# MCU.net
KiCad netlist of a schematic drawn in Altium Designer
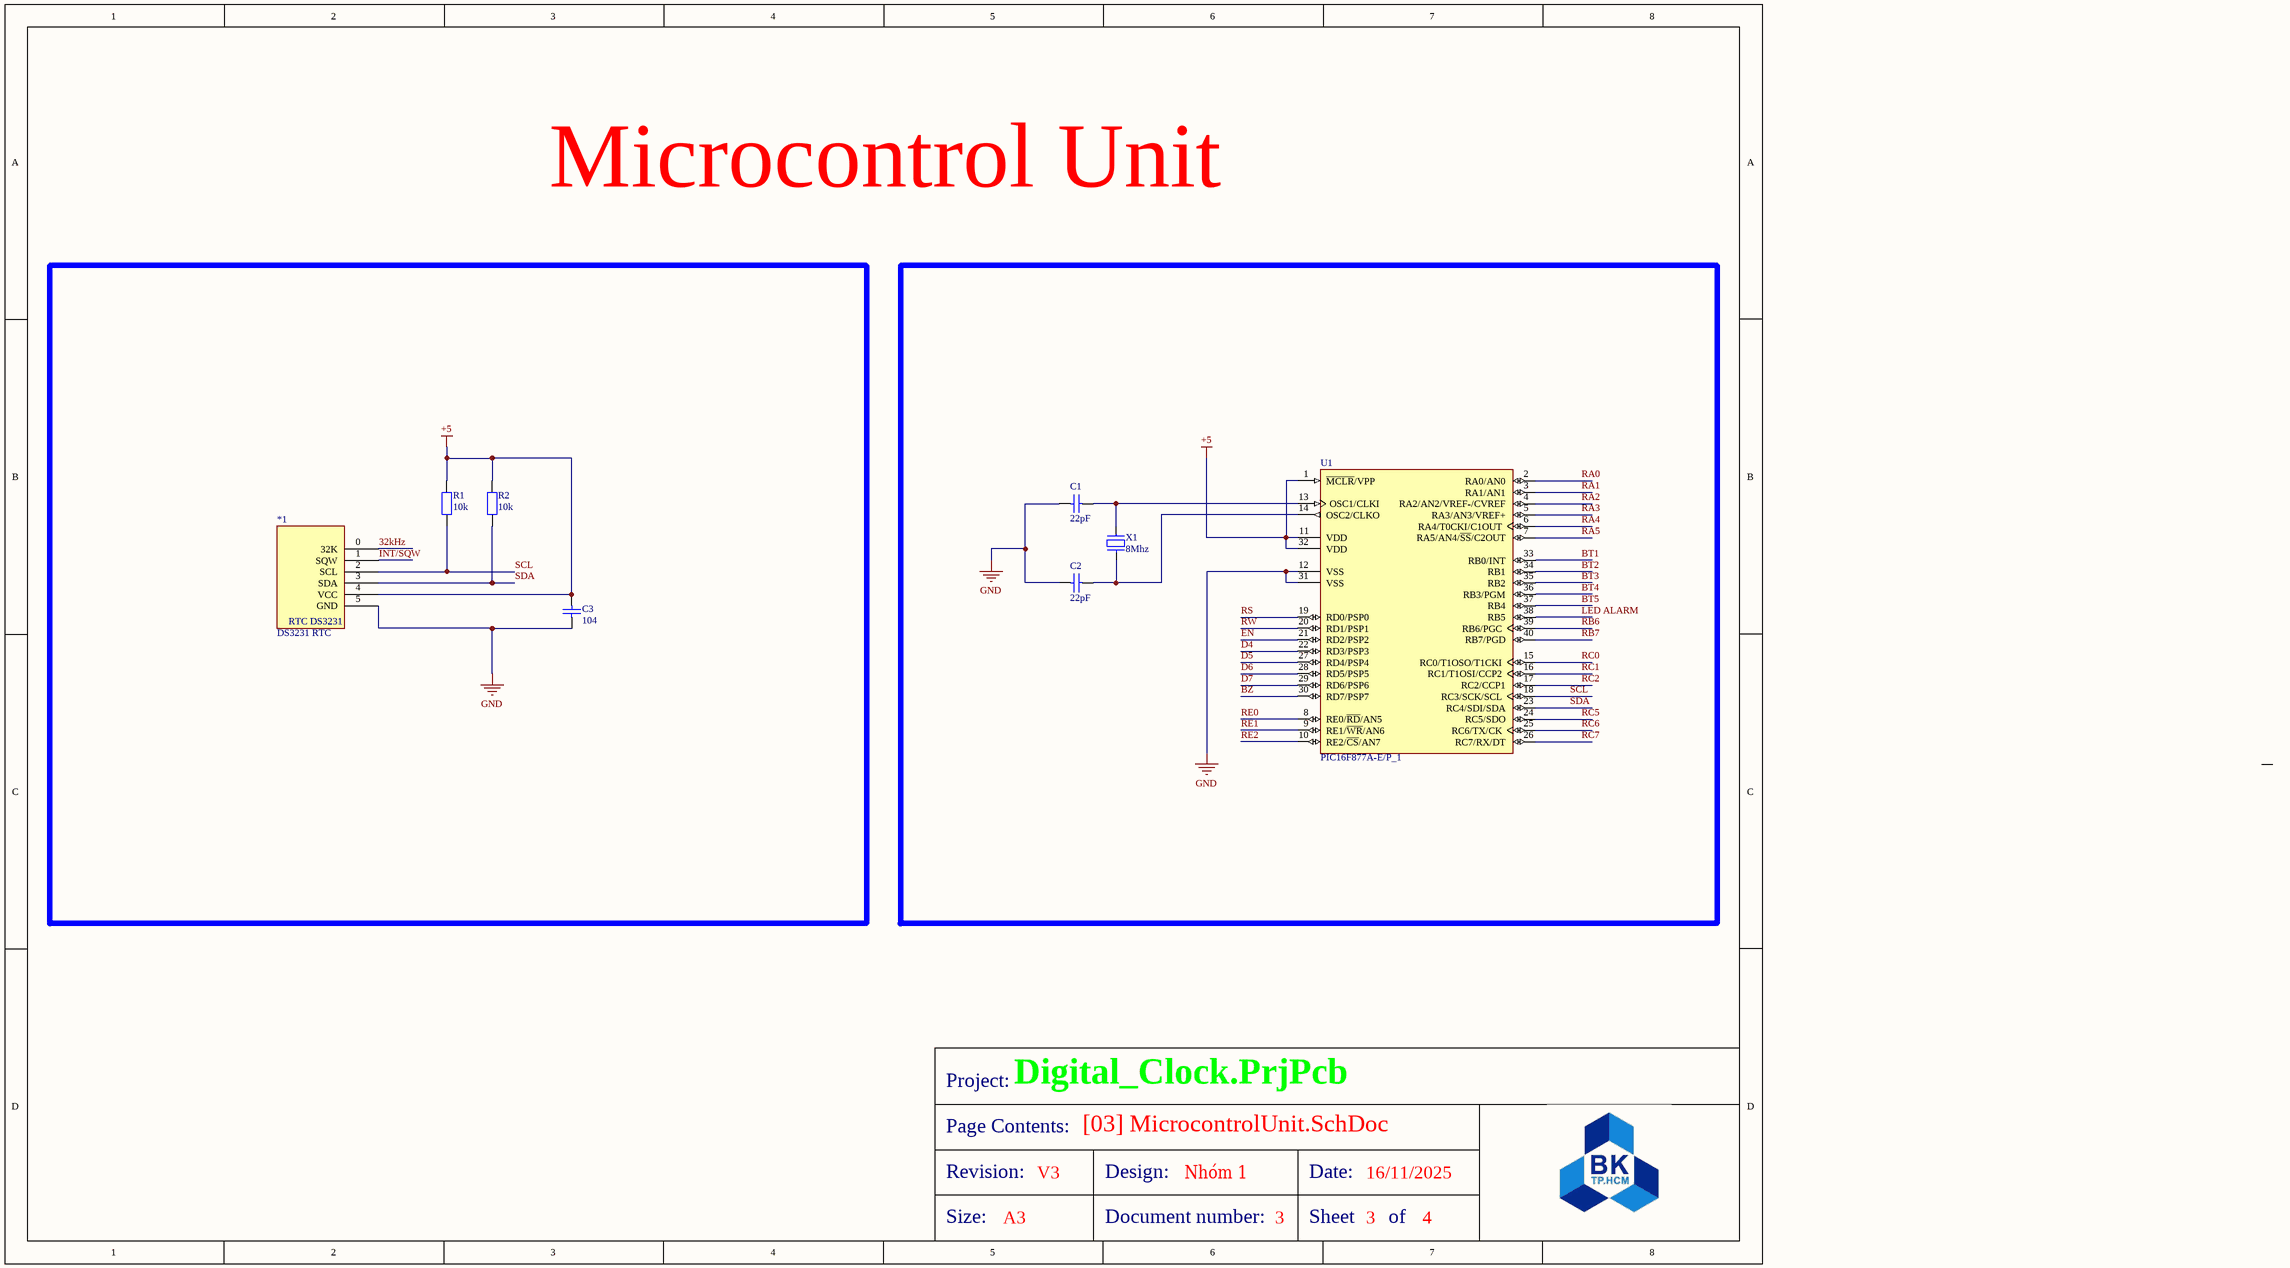
[diagram p0: MCU.SchDoc]

(export (version "E")
  (design (tool "Eeschema 10.0.6"))
  (components
    (comp (ref "*1")
      (value "DS3231 RTC")
      (footprint "2RTC-DS3231-MODULE")
      (libsource (lib "lk") (part "DS3231 RTC"))
    )
    (comp (ref "C1")
      (value "22pF")
      (footprint "tu gom")
      (description "Cắm")
      (libsource (lib "Capacitor") (part "Tu gom 22pF 50V"))
    )
    (comp (ref "C2")
      (value "22pF")
      (footprint "tu gom")
      (description "Cắm")
      (libsource (lib "Capacitor") (part "Tu gom 22pF 50V"))
    )
    (comp (ref "C3")
      (value "104")
      (footprint "tu gom")
      (description "Cắm")
      (libsource (lib "Capacitor") (part "Tu gom 104 50V"))
    )
    (comp (ref "R1")
      (value "10k")
      (footprint "R1/4W")
      (description "Resistor 1/4W")
      (libsource (lib "My Library") (part "R1/4W"))
    )
    (comp (ref "R2")
      (value "10k")
      (footprint "R1/4W")
      (description "Resistor 1/4W")
      (libsource (lib "My Library") (part "R1/4W"))
    )
    (comp (ref "U1")
      (value "PIC16F877A-E/P_1")
      (footprint "PDIP600-P40")
      (fields (field (name "PUBLISHER") "Altium Limited"))
      (libsource (lib "Cty1") (part "PIC16F877A-E/P_1"))
    )
    (comp (ref "X1")
      (value "8Mhz")
      (footprint "XT2")
      (description "Crystal For all Crystal 2pin.")
      (libsource (lib "Digital Watch") (part "XT2"))
    )
  )
  (nets
    (net (code "1") (name "+5") (class "Default")
      (node (ref "*1") (pin "4") (pinfunction "VCC_4") (pintype "power_in"))
      (node (ref "C3") (pin "1") (pinfunction "1_1") (pintype "passive"))
      (node (ref "R1") (pin "2") (pinfunction "2_2") (pintype "passive"))
      (node (ref "R2") (pin "2") (pinfunction "2_2") (pintype "passive"))
      (node (ref "U1") (pin "1") (pinfunction "~{MCLR}/VPP_1") (pintype "input"))
      (node (ref "U1") (pin "11") (pinfunction "VDD_11") (pintype "power_in"))
      (node (ref "U1") (pin "32") (pinfunction "VDD_32") (pintype "power_in"))
    )
    (net (code "2") (name "/32kHz") (class "Default")
      (node (ref "*1") (pin "0") (pinfunction "32K_0") (pintype "passive"))
    )
    (net (code "3") (name "/BT1") (class "Default")
      (node (ref "U1") (pin "33") (pinfunction "RB0/INT_33") (pintype "bidirectional"))
    )
    (net (code "4") (name "/BT2") (class "Default")
      (node (ref "U1") (pin "34") (pinfunction "RB1_34") (pintype "bidirectional"))
    )
    (net (code "5") (name "/BT3") (class "Default")
      (node (ref "U1") (pin "35") (pinfunction "RB2_35") (pintype "bidirectional"))
    )
    (net (code "6") (name "/BT4") (class "Default")
      (node (ref "U1") (pin "36") (pinfunction "RB3/PGM_36") (pintype "bidirectional"))
    )
    (net (code "7") (name "/BT5") (class "Default")
      (node (ref "U1") (pin "37") (pinfunction "RB4_37") (pintype "bidirectional"))
    )
    (net (code "8") (name "/BZ") (class "Default")
      (node (ref "U1") (pin "30") (pinfunction "RD7/PSP7_30") (pintype "bidirectional"))
    )
    (net (code "9") (name "/D4") (class "Default")
      (node (ref "U1") (pin "22") (pinfunction "RD3/PSP3_22") (pintype "bidirectional"))
    )
    (net (code "10") (name "/D5") (class "Default")
      (node (ref "U1") (pin "27") (pinfunction "RD4/PSP4_27") (pintype "bidirectional"))
    )
    (net (code "11") (name "/D6") (class "Default")
      (node (ref "U1") (pin "28") (pinfunction "RD5/PSP5_28") (pintype "bidirectional"))
    )
    (net (code "12") (name "/D7") (class "Default")
      (node (ref "U1") (pin "29") (pinfunction "RD6/PSP6_29") (pintype "bidirectional"))
    )
    (net (code "13") (name "/EN") (class "Default")
      (node (ref "U1") (pin "21") (pinfunction "RD2/PSP2_21") (pintype "bidirectional"))
    )
    (net (code "14") (name "/INT{slash}SQW") (class "Default")
      (node (ref "*1") (pin "1") (pinfunction "SQW_1") (pintype "passive"))
    )
    (net (code "15") (name "/LED ALARM") (class "Default")
      (node (ref "U1") (pin "38") (pinfunction "RB5_38") (pintype "bidirectional"))
    )
    (net (code "16") (name "/RA0") (class "Default")
      (node (ref "U1") (pin "2") (pinfunction "RA0/AN0_2") (pintype "bidirectional"))
    )
    (net (code "17") (name "/RA1") (class "Default")
      (node (ref "U1") (pin "3") (pinfunction "RA1/AN1_3") (pintype "bidirectional"))
    )
    (net (code "18") (name "/RA2") (class "Default")
      (node (ref "U1") (pin "4") (pinfunction "RA2/AN2/VREF-/CVREF_4") (pintype "bidirectional"))
    )
    (net (code "19") (name "/RA3") (class "Default")
      (node (ref "U1") (pin "5") (pinfunction "RA3/AN3/VREF+_5") (pintype "bidirectional"))
    )
    (net (code "20") (name "/RA4") (class "Default")
      (node (ref "U1") (pin "6") (pinfunction "RA4/T0CKI/C1OUT_6") (pintype "bidirectional"))
    )
    (net (code "21") (name "/RA5") (class "Default")
      (node (ref "U1") (pin "7") (pinfunction "RA5/AN4/~{SS}/C2OUT_7") (pintype "bidirectional"))
    )
    (net (code "22") (name "/RB6") (class "Default")
      (node (ref "U1") (pin "39") (pinfunction "RB6/PGC_39") (pintype "bidirectional"))
    )
    (net (code "23") (name "/RB7") (class "Default")
      (node (ref "U1") (pin "40") (pinfunction "RB7/PGD_40") (pintype "bidirectional"))
    )
    (net (code "24") (name "/RC0") (class "Default")
      (node (ref "U1") (pin "15") (pinfunction "RC0/T1OSO/T1CKI_15") (pintype "bidirectional"))
    )
    (net (code "25") (name "/RC1") (class "Default")
      (node (ref "U1") (pin "16") (pinfunction "RC1/T1OSI/CCP2_16") (pintype "bidirectional"))
    )
    (net (code "26") (name "/RC2") (class "Default")
      (node (ref "U1") (pin "17") (pinfunction "RC2/CCP1_17") (pintype "bidirectional"))
    )
    (net (code "27") (name "/RC5") (class "Default")
      (node (ref "U1") (pin "24") (pinfunction "RC5/SDO_24") (pintype "bidirectional"))
    )
    (net (code "28") (name "/RC6") (class "Default")
      (node (ref "U1") (pin "25") (pinfunction "RC6/TX/CK_25") (pintype "bidirectional"))
    )
    (net (code "29") (name "/RC7") (class "Default")
      (node (ref "U1") (pin "26") (pinfunction "RC7/RX/DT_26") (pintype "bidirectional"))
    )
    (net (code "30") (name "/RE0") (class "Default")
      (node (ref "U1") (pin "8") (pinfunction "RE0/~{RD}/AN5_8") (pintype "bidirectional"))
    )
    (net (code "31") (name "/RE1") (class "Default")
      (node (ref "U1") (pin "9") (pinfunction "RE1/~{WR}/AN6_9") (pintype "bidirectional"))
    )
    (net (code "32") (name "/RE2") (class "Default")
      (node (ref "U1") (pin "10") (pinfunction "RE2/~{CS}/AN7_10") (pintype "bidirectional"))
    )
    (net (code "33") (name "/RS") (class "Default")
      (node (ref "U1") (pin "19") (pinfunction "RD0/PSP0_19") (pintype "bidirectional"))
    )
    (net (code "34") (name "/RW") (class "Default")
      (node (ref "U1") (pin "20") (pinfunction "RD1/PSP1_20") (pintype "bidirectional"))
    )
    (net (code "35") (name "/SCL") (class "Default")
      (node (ref "*1") (pin "2") (pinfunction "SCL_2") (pintype "passive"))
      (node (ref "R1") (pin "1") (pinfunction "1_1") (pintype "passive"))
      (node (ref "U1") (pin "18") (pinfunction "RC3/SCK/SCL_18") (pintype "bidirectional"))
    )
    (net (code "36") (name "/SDA") (class "Default")
      (node (ref "*1") (pin "3") (pinfunction "SDA_3") (pintype "passive"))
      (node (ref "R2") (pin "1") (pinfunction "1_1") (pintype "passive"))
      (node (ref "U1") (pin "23") (pinfunction "RC4/SDI/SDA_23") (pintype "bidirectional"))
    )
    (net (code "37") (name "GND") (class "Default")
      (node (ref "*1") (pin "5") (pinfunction "GND_5") (pintype "power_in"))
      (node (ref "C1") (pin "2") (pinfunction "2_2") (pintype "passive"))
      (node (ref "C2") (pin "2") (pinfunction "2_2") (pintype "passive"))
      (node (ref "C3") (pin "2") (pinfunction "2_2") (pintype "passive"))
      (node (ref "U1") (pin "12") (pinfunction "VSS_12") (pintype "power_in"))
      (node (ref "U1") (pin "31") (pinfunction "VSS_31") (pintype "power_in"))
    )
    (net (code "38") (name "Net-(U1-OSC1{slash}CLKI)") (class "Default")
      (node (ref "C1") (pin "1") (pinfunction "1_1") (pintype "passive"))
      (node (ref "U1") (pin "13") (pinfunction "OSC1/CLKI_13") (pintype "input"))
      (node (ref "X1") (pin "1") (pinfunction "1_1") (pintype "passive"))
    )
    (net (code "39") (name "Net-(U1-OSC2{slash}CLKO)") (class "Default")
      (node (ref "C2") (pin "1") (pinfunction "1_1") (pintype "passive"))
      (node (ref "U1") (pin "14") (pinfunction "OSC2/CLKO_14") (pintype "output"))
      (node (ref "X1") (pin "2") (pinfunction "2_2") (pintype "passive"))
    )
  )
)
